# Busswitch_-_Copy.net
KiCad netlist of a schematic drawn in Altium Designer
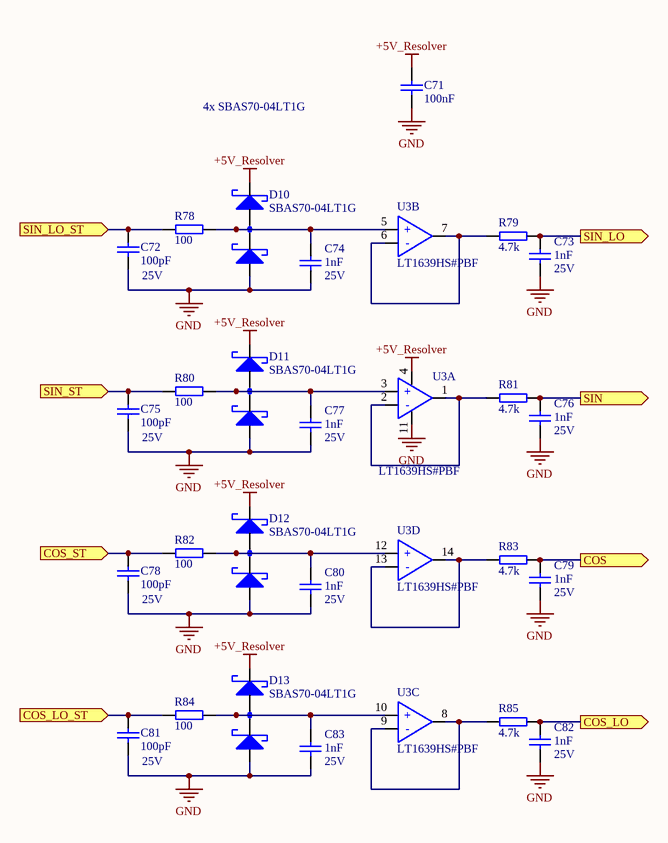
[diagram p0: Busswitch - Copy.SchDoc]

(export (version "E")
  (design (tool "Eeschema 10.0.6"))
  (components
    (comp (ref "C71")
      (value "100nF")
      (footprint "CAPC1608X07N")
      (fields (field (name "MF") "Würth") (field (name "MPN") "885012206071") (field (name "VOLTAGE") "25V"))
      (libsource (lib "UltraZohm_ADC") (part "Cap_0603"))
    )
    (comp (ref "C72")
      (value "100pF")
      (footprint "CAPC1608X07N")
      (fields (field (name "VOLTAGE") "25V"))
      (libsource (lib "UltraZohm_ADC") (part "Cap_0603"))
    )
    (comp (ref "C73")
      (value "1nF")
      (footprint "CAPC1608X07N")
      (fields (field (name "VOLTAGE") "25V"))
      (libsource (lib "UltraZohm_ADC") (part "Cap_0603"))
    )
    (comp (ref "C74")
      (value "1nF")
      (footprint "CAPC1608X07N")
      (fields (field (name "VOLTAGE") "25V"))
      (libsource (lib "UltraZohm_ADC") (part "Cap_0603"))
    )
    (comp (ref "C75")
      (value "100pF")
      (footprint "CAPC1608X07N")
      (fields (field (name "VOLTAGE") "25V"))
      (libsource (lib "UltraZohm_ADC") (part "Cap_0603"))
    )
    (comp (ref "C76")
      (value "1nF")
      (footprint "CAPC1608X07N")
      (fields (field (name "VOLTAGE") "25V"))
      (libsource (lib "UltraZohm_ADC") (part "Cap_0603"))
    )
    (comp (ref "C77")
      (value "1nF")
      (footprint "CAPC1608X07N")
      (fields (field (name "VOLTAGE") "25V"))
      (libsource (lib "UltraZohm_ADC") (part "Cap_0603"))
    )
    (comp (ref "C78")
      (value "100pF")
      (footprint "CAPC1608X07N")
      (fields (field (name "VOLTAGE") "25V"))
      (libsource (lib "UltraZohm_ADC") (part "Cap_0603"))
    )
    (comp (ref "C79")
      (value "1nF")
      (footprint "CAPC1608X07N")
      (fields (field (name "VOLTAGE") "25V"))
      (libsource (lib "UltraZohm_ADC") (part "Cap_0603"))
    )
    (comp (ref "C80")
      (value "1nF")
      (footprint "CAPC1608X07N")
      (fields (field (name "VOLTAGE") "25V"))
      (libsource (lib "UltraZohm_ADC") (part "Cap_0603"))
    )
    (comp (ref "C81")
      (value "100pF")
      (footprint "CAPC1608X07N")
      (fields (field (name "VOLTAGE") "25V"))
      (libsource (lib "UltraZohm_ADC") (part "Cap_0603"))
    )
    (comp (ref "C82")
      (value "1nF")
      (footprint "CAPC1608X07N")
      (fields (field (name "VOLTAGE") "25V"))
      (libsource (lib "UltraZohm_ADC") (part "Cap_0603"))
    )
    (comp (ref "C83")
      (value "1nF")
      (footprint "CAPC1608X07N")
      (fields (field (name "VOLTAGE") "25V"))
      (libsource (lib "UltraZohm_ADC") (part "Cap_0603"))
    )
    (comp (ref "D10")
      (value "SBAS70-04LT1G")
      (footprint "SOT-23")
      (description "DIODE SCHOTTKY 70V DUAL SOT23")
      (fields (field (name "MF") "ON Semiconductor"))
      (libsource (lib "Componentes_SOC") (part "Diode Array Schottky"))
    )
    (comp (ref "D11")
      (value "SBAS70-04LT1G")
      (footprint "SOT-23")
      (description "DIODE SCHOTTKY 70V DUAL SOT23")
      (fields (field (name "MF") "ON Semiconductor"))
      (libsource (lib "Componentes_SOC") (part "Diode Array Schottky"))
    )
    (comp (ref "D12")
      (value "SBAS70-04LT1G")
      (footprint "SOT-23")
      (description "DIODE SCHOTTKY 70V DUAL SOT23")
      (fields (field (name "MF") "ON Semiconductor"))
      (libsource (lib "Componentes_SOC") (part "Diode Array Schottky"))
    )
    (comp (ref "D13")
      (value "SBAS70-04LT1G")
      (footprint "SOT-23")
      (description "DIODE SCHOTTKY 70V DUAL SOT23")
      (fields (field (name "MF") "ON Semiconductor"))
      (libsource (lib "Componentes_SOC") (part "Diode Array Schottky"))
    )
    (comp (ref "R78")
      (value "100")
      (footprint "RESC1608X06N")
      (libsource (lib "UltraZohm_ADC") (part "R_0603"))
    )
    (comp (ref "R79")
      (value "4.7k")
      (footprint "RESC1608X06N")
      (libsource (lib "UltraZohm_ADC") (part "R_0603"))
    )
    (comp (ref "R80")
      (value "100")
      (footprint "RESC1608X06N")
      (libsource (lib "UltraZohm_ADC") (part "R_0603"))
    )
    (comp (ref "R81")
      (value "4.7k")
      (footprint "RESC1608X06N")
      (libsource (lib "UltraZohm_ADC") (part "R_0603"))
    )
    (comp (ref "R82")
      (value "100")
      (footprint "RESC1608X06N")
      (libsource (lib "UltraZohm_ADC") (part "R_0603"))
    )
    (comp (ref "R83")
      (value "4.7k")
      (footprint "RESC1608X06N")
      (libsource (lib "UltraZohm_ADC") (part "R_0603"))
    )
    (comp (ref "R84")
      (value "100")
      (footprint "RESC1608X06N")
      (libsource (lib "UltraZohm_ADC") (part "R_0603"))
    )
    (comp (ref "R85")
      (value "4.7k")
      (footprint "RESC1608X06N")
      (libsource (lib "UltraZohm_ADC") (part "R_0603"))
    )
    (comp (ref "U3")
      (value "LT1639HS#PBF")
      (footprint "SOIC-14")
      (description "IC OPAMP GP 4 CIRCUIT 14SO")
      (fields (field (name "MF") "Analog Devices"))
      (libsource (lib "Componentes_SOC") (part "LT1639"))
    )
  )
  (nets
    (net (code "1") (name "+5V_Resolver") (class "Default")
      (node (ref "C71") (pin "1") (pinfunction "1_1") (pintype "passive"))
      (node (ref "D10") (pin "2") (pintype "passive"))
      (node (ref "D11") (pin "2") (pintype "passive"))
      (node (ref "D12") (pin "2") (pintype "passive"))
      (node (ref "D13") (pin "2") (pintype "passive"))
      (node (ref "U3") (pin "4") (pinfunction "V+_4") (pintype "passive"))
    )
    (net (code "2") (name "/COS") (class "Default")
      (node (ref "C79") (pin "1") (pinfunction "1_1") (pintype "passive"))
      (node (ref "R83") (pin "2") (pintype "passive"))
    )
    (net (code "3") (name "/COS_LO") (class "Default")
      (node (ref "C82") (pin "1") (pinfunction "1_1") (pintype "passive"))
      (node (ref "R85") (pin "2") (pintype "passive"))
    )
    (net (code "4") (name "/COS_LO_ST") (class "Default")
      (node (ref "C81") (pin "1") (pinfunction "1_1") (pintype "passive"))
      (node (ref "R84") (pin "1") (pintype "passive"))
    )
    (net (code "5") (name "/COS_ST") (class "Default")
      (node (ref "C78") (pin "1") (pinfunction "1_1") (pintype "passive"))
      (node (ref "R82") (pin "1") (pintype "passive"))
    )
    (net (code "6") (name "/SIN") (class "Default")
      (node (ref "C76") (pin "1") (pinfunction "1_1") (pintype "passive"))
      (node (ref "R81") (pin "2") (pintype "passive"))
    )
    (net (code "7") (name "/SIN_LO") (class "Default")
      (node (ref "C73") (pin "1") (pinfunction "1_1") (pintype "passive"))
      (node (ref "R79") (pin "2") (pintype "passive"))
    )
    (net (code "8") (name "/SIN_LO_ST") (class "Default")
      (node (ref "C72") (pin "1") (pinfunction "1_1") (pintype "passive"))
      (node (ref "R78") (pin "1") (pintype "passive"))
    )
    (net (code "9") (name "/SIN_ST") (class "Default")
      (node (ref "C75") (pin "1") (pinfunction "1_1") (pintype "passive"))
      (node (ref "R80") (pin "1") (pintype "passive"))
    )
    (net (code "10") (name "GND") (class "Default")
      (node (ref "C71") (pin "2") (pinfunction "2_2") (pintype "passive"))
      (node (ref "C72") (pin "2") (pinfunction "2_2") (pintype "passive"))
      (node (ref "C73") (pin "2") (pinfunction "2_2") (pintype "passive"))
      (node (ref "C74") (pin "2") (pinfunction "2_2") (pintype "passive"))
      (node (ref "C75") (pin "2") (pinfunction "2_2") (pintype "passive"))
      (node (ref "C76") (pin "2") (pinfunction "2_2") (pintype "passive"))
      (node (ref "C77") (pin "2") (pinfunction "2_2") (pintype "passive"))
      (node (ref "C78") (pin "2") (pinfunction "2_2") (pintype "passive"))
      (node (ref "C79") (pin "2") (pinfunction "2_2") (pintype "passive"))
      (node (ref "C80") (pin "2") (pinfunction "2_2") (pintype "passive"))
      (node (ref "C81") (pin "2") (pinfunction "2_2") (pintype "passive"))
      (node (ref "C82") (pin "2") (pinfunction "2_2") (pintype "passive"))
      (node (ref "C83") (pin "2") (pinfunction "2_2") (pintype "passive"))
      (node (ref "D10") (pin "1") (pintype "passive"))
      (node (ref "D11") (pin "1") (pintype "passive"))
      (node (ref "D12") (pin "1") (pintype "passive"))
      (node (ref "D13") (pin "1") (pintype "passive"))
      (node (ref "U3") (pin "11") (pinfunction "V-_11") (pintype "passive"))
    )
    (net (code "11") (name "Net-(U3A-+)") (class "Default")
      (node (ref "C77") (pin "1") (pinfunction "1_1") (pintype "passive"))
      (node (ref "D11") (pin "3") (pintype "passive"))
      (node (ref "R80") (pin "2") (pintype "passive"))
      (node (ref "U3") (pin "3") (pinfunction "+_3") (pintype "passive"))
    )
    (net (code "12") (name "Net-(U3A--)") (class "Default")
      (node (ref "R81") (pin "1") (pintype "passive"))
      (node (ref "U3") (pin "1") (pintype "passive"))
      (node (ref "U3") (pin "2") (pinfunction "-_2") (pintype "passive"))
    )
    (net (code "13") (name "Net-(U3B-+)") (class "Default")
      (node (ref "C74") (pin "1") (pinfunction "1_1") (pintype "passive"))
      (node (ref "D10") (pin "3") (pintype "passive"))
      (node (ref "R78") (pin "2") (pintype "passive"))
      (node (ref "U3") (pin "5") (pinfunction "+_5") (pintype "passive"))
    )
    (net (code "14") (name "Net-(U3B--)") (class "Default")
      (node (ref "R79") (pin "1") (pintype "passive"))
      (node (ref "U3") (pin "6") (pinfunction "-_6") (pintype "passive"))
      (node (ref "U3") (pin "7") (pintype "passive"))
    )
    (net (code "15") (name "Net-(U3C-+)") (class "Default")
      (node (ref "C83") (pin "1") (pinfunction "1_1") (pintype "passive"))
      (node (ref "D13") (pin "3") (pintype "passive"))
      (node (ref "R84") (pin "2") (pintype "passive"))
      (node (ref "U3") (pin "10") (pinfunction "+_10") (pintype "passive"))
    )
    (net (code "16") (name "Net-(U3C--)") (class "Default")
      (node (ref "R85") (pin "1") (pintype "passive"))
      (node (ref "U3") (pin "8") (pintype "passive"))
      (node (ref "U3") (pin "9") (pinfunction "-_9") (pintype "passive"))
    )
    (net (code "17") (name "Net-(U3D-+)") (class "Default")
      (node (ref "C80") (pin "1") (pinfunction "1_1") (pintype "passive"))
      (node (ref "D12") (pin "3") (pintype "passive"))
      (node (ref "R82") (pin "2") (pintype "passive"))
      (node (ref "U3") (pin "12") (pinfunction "+_12") (pintype "passive"))
    )
    (net (code "18") (name "Net-(U3D--)") (class "Default")
      (node (ref "R83") (pin "1") (pintype "passive"))
      (node (ref "U3") (pin "13") (pinfunction "-_13") (pintype "passive"))
      (node (ref "U3") (pin "14") (pintype "passive"))
    )
  )
)
